# Headers.net
KiCad netlist of a schematic drawn in Altium Designer
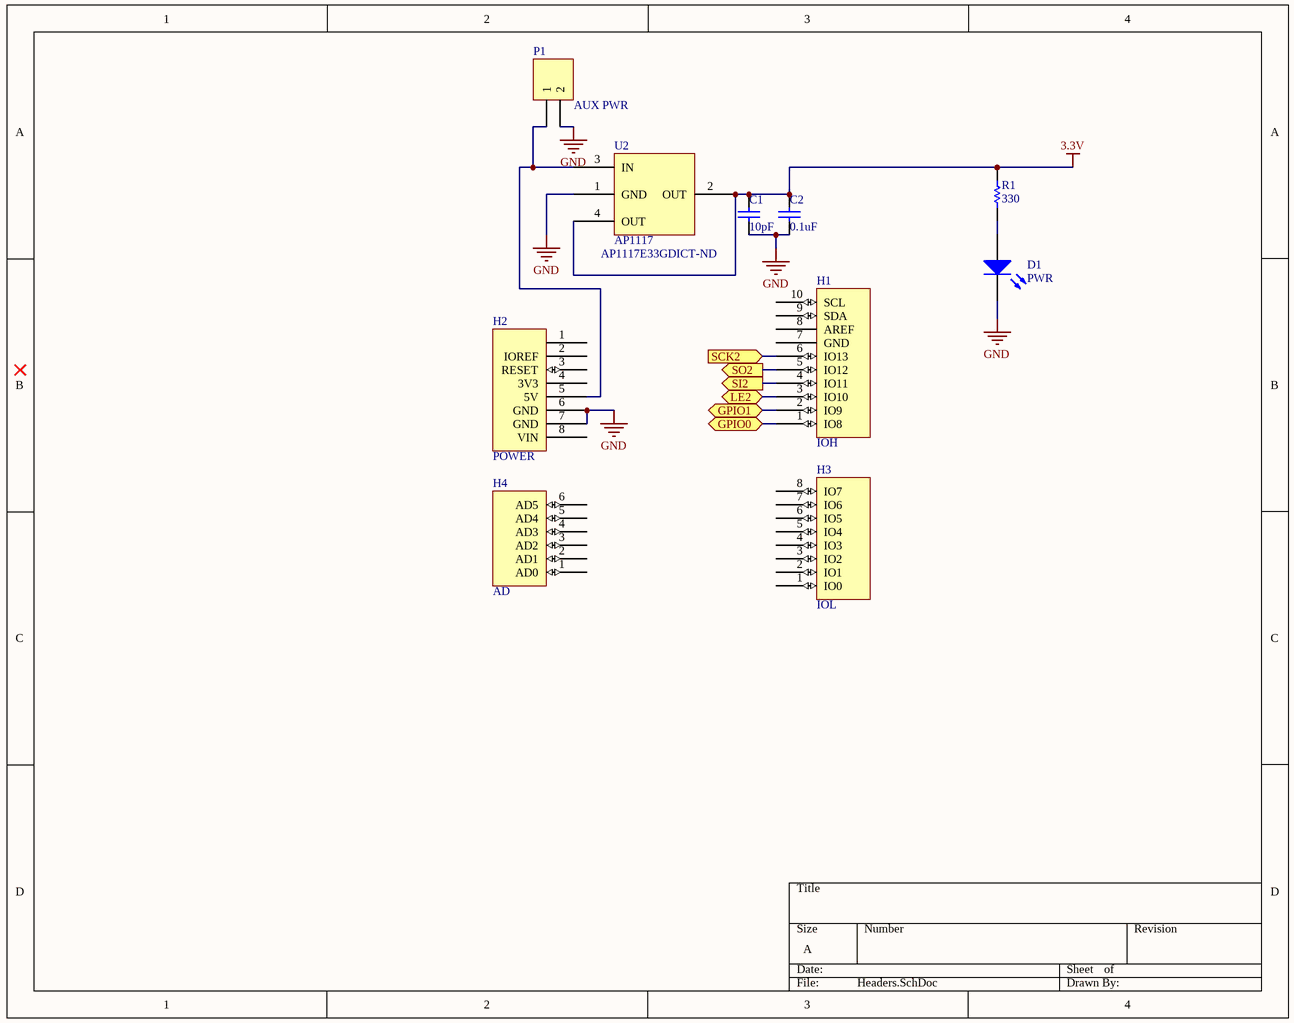
[diagram p0: Headers.SchDoc]

(export (version "E")
  (design (tool "Eeschema 10.0.6"))
  (components
    (comp (ref "C1")
      (value "10pF")
      (footprint "0402")
      (description "Capacitor (Semiconductor SIM Model)")
      (fields (field (name "Comment") "Cap Semi") (field (name "PUBLISHER") "Altium Limited"))
      (libsource (lib "Miscellaneous Devices") (part "Cap Semi"))
    )
    (comp (ref "C2")
      (value "0.1uF")
      (footprint "0402")
      (description "Capacitor (Semiconductor SIM Model)")
      (fields (field (name "Comment") "Cap Semi") (field (name "PUBLISHER") "Altium Limited"))
      (libsource (lib "Miscellaneous Devices") (part "Cap Semi"))
    )
    (comp (ref "D1")
      (value "PWR")
      (footprint "0603")
      (description "Typical RED, GREEN, YELLOW, AMBER GaAs LED")
      (fields (field (name "PUBLISHER") "Altium Limited"))
      (libsource (lib "Miscellaneous Devices") (part "LED2"))
    )
    (comp (ref "H1")
      (value "IOH")
      (footprint "Header:Header 10x1 8.5mm")
      (libsource (lib "Header") (part "IOH"))
    )
    (comp (ref "H2")
      (value "POWER")
      (footprint "Header:Header 8x1 8.5mm")
      (libsource (lib "Header") (part "POWER"))
    )
    (comp (ref "H3")
      (value "IOL")
      (footprint "Header:Header 8x1 8.5mm")
      (libsource (lib "Header") (part "IOL"))
    )
    (comp (ref "H4")
      (value "AD")
      (footprint "Header:Header 6x1 8.5mm")
      (libsource (lib "Header") (part "AD"))
    )
    (comp (ref "P1")
      (value "AUX PWR")
      (footprint "HDR1X2")
      (description "Header, 2-Pin")
      (fields (field (name "PUBLISHER") "Altium Limited"))
      (libsource (lib "Miscellaneous Connectors") (part "Header 2"))
    )
    (comp (ref "R1")
      (value "330")
      (footprint "0402")
      (description "Semiconductor Resistor")
      (fields (field (name "Comment") "Res Semi") (field (name "PUBLISHER") "Altium Limited"))
      (libsource (lib "Miscellaneous Devices") (part "Res Semi"))
    )
    (comp (ref "U2") (value "AP1117") (libsource (lib "shield_components") (part "AP1117")))
  )
  (nets
    (net (code "1") (name "/GPIO0") (class "Default")
      (node (ref "H1") (pin "1") (pinfunction "IO8_1") (pintype "bidirectional"))
    )
    (net (code "2") (name "/GPIO1") (class "Default")
      (node (ref "H1") (pin "2") (pinfunction "IO9_2") (pintype "bidirectional"))
    )
    (net (code "3") (name "/LE2") (class "Default")
      (node (ref "H1") (pin "3") (pinfunction "IO10_3") (pintype "bidirectional"))
    )
    (net (code "4") (name "/SCK2") (class "Default")
      (node (ref "H1") (pin "6") (pinfunction "IO13_6") (pintype "bidirectional"))
    )
    (net (code "5") (name "/SI2") (class "Default")
      (node (ref "H1") (pin "4") (pinfunction "IO11_4") (pintype "bidirectional"))
    )
    (net (code "6") (name "/SO2") (class "Default")
      (node (ref "H1") (pin "5") (pinfunction "IO12_5") (pintype "bidirectional"))
    )
    (net (code "7") (name "3.3V") (class "Default")
      (node (ref "C1") (pin "1") (pinfunction "1_1") (pintype "passive"))
      (node (ref "C2") (pin "1") (pinfunction "1_1") (pintype "passive"))
      (node (ref "R1") (pin "2") (pinfunction "2_2") (pintype "passive"))
      (node (ref "U2") (pin "2") (pinfunction "OUT_2") (pintype "passive"))
      (node (ref "U2") (pin "4") (pinfunction "OUT_4") (pintype "passive"))
    )
    (net (code "8") (name "GND") (class "Default")
      (node (ref "C1") (pin "2") (pinfunction "2_2") (pintype "passive"))
      (node (ref "C2") (pin "2") (pinfunction "2_2") (pintype "passive"))
      (node (ref "D1") (pin "2") (pinfunction "K_2") (pintype "passive"))
      (node (ref "H2") (pin "6") (pinfunction "GND_6") (pintype "power_in"))
      (node (ref "H2") (pin "7") (pinfunction "GND_7") (pintype "power_in"))
      (node (ref "P1") (pin "2") (pinfunction "2_2") (pintype "passive"))
      (node (ref "U2") (pin "1") (pinfunction "GND_1") (pintype "passive"))
    )
    (net (code "9") (name "Net-(D1-A)") (class "Default")
      (node (ref "D1") (pin "1") (pinfunction "A_1") (pintype "passive"))
      (node (ref "R1") (pin "1") (pinfunction "1_1") (pintype "passive"))
    )
    (net (code "10") (name "Net-(H2-5V)") (class "Default")
      (node (ref "H2") (pin "5") (pinfunction "5V_5") (pintype "power_in"))
      (node (ref "P1") (pin "1") (pinfunction "1_1") (pintype "passive"))
      (node (ref "U2") (pin "3") (pinfunction "IN_3") (pintype "passive"))
    )
    (net (code "11") (name "unconnected-(H1-AREF-Pad8)") (class "Default")
      (node (ref "H1") (pin "8") (pinfunction "AREF_8") (pintype "passive"))
    )
    (net (code "12") (name "unconnected-(H1-GND-Pad7)") (class "Default")
      (node (ref "H1") (pin "7") (pinfunction "GND_7") (pintype "power_in"))
    )
    (net (code "13") (name "unconnected-(H1-SCL-Pad10)") (class "Default")
      (node (ref "H1") (pin "10") (pinfunction "SCL_10") (pintype "bidirectional"))
    )
    (net (code "14") (name "unconnected-(H1-SDA-Pad9)") (class "Default")
      (node (ref "H1") (pin "9") (pinfunction "SDA_9") (pintype "bidirectional"))
    )
    (net (code "15") (name "unconnected-(H2-3V3-Pad4)") (class "Default")
      (node (ref "H2") (pin "4") (pinfunction "3V3_4") (pintype "power_in"))
    )
    (net (code "16") (name "unconnected-(H2-IOREF-Pad2)") (class "Default")
      (node (ref "H2") (pin "2") (pinfunction "IOREF_2") (pintype "power_in"))
    )
    (net (code "17") (name "unconnected-(H2-Pad1)") (class "Default")
      (node (ref "H2") (pin "1") (pintype "passive"))
    )
    (net (code "18") (name "unconnected-(H2-RESET-Pad3)") (class "Default")
      (node (ref "H2") (pin "3") (pinfunction "RESET_3") (pintype "bidirectional"))
    )
    (net (code "19") (name "unconnected-(H2-VIN-Pad8)") (class "Default")
      (node (ref "H2") (pin "8") (pinfunction "VIN_8") (pintype "power_in"))
    )
    (net (code "20") (name "unconnected-(H3-IO0-Pad1)") (class "Default")
      (node (ref "H3") (pin "1") (pinfunction "IO0_1") (pintype "bidirectional"))
    )
    (net (code "21") (name "unconnected-(H3-IO1-Pad2)") (class "Default")
      (node (ref "H3") (pin "2") (pinfunction "IO1_2") (pintype "bidirectional"))
    )
    (net (code "22") (name "unconnected-(H3-IO2-Pad3)") (class "Default")
      (node (ref "H3") (pin "3") (pinfunction "IO2_3") (pintype "bidirectional"))
    )
    (net (code "23") (name "unconnected-(H3-IO3-Pad4)") (class "Default")
      (node (ref "H3") (pin "4") (pinfunction "IO3_4") (pintype "bidirectional"))
    )
    (net (code "24") (name "unconnected-(H3-IO4-Pad5)") (class "Default")
      (node (ref "H3") (pin "5") (pinfunction "IO4_5") (pintype "bidirectional"))
    )
    (net (code "25") (name "unconnected-(H3-IO5-Pad6)") (class "Default")
      (node (ref "H3") (pin "6") (pinfunction "IO5_6") (pintype "bidirectional"))
    )
    (net (code "26") (name "unconnected-(H3-IO6-Pad7)") (class "Default")
      (node (ref "H3") (pin "7") (pinfunction "IO6_7") (pintype "bidirectional"))
    )
    (net (code "27") (name "unconnected-(H3-IO7-Pad8)") (class "Default")
      (node (ref "H3") (pin "8") (pinfunction "IO7_8") (pintype "bidirectional"))
    )
    (net (code "28") (name "unconnected-(H4-AD0-Pad1)") (class "Default")
      (node (ref "H4") (pin "1") (pinfunction "AD0_1") (pintype "bidirectional"))
    )
    (net (code "29") (name "unconnected-(H4-AD1-Pad2)") (class "Default")
      (node (ref "H4") (pin "2") (pinfunction "AD1_2") (pintype "bidirectional"))
    )
    (net (code "30") (name "unconnected-(H4-AD2-Pad3)") (class "Default")
      (node (ref "H4") (pin "3") (pinfunction "AD2_3") (pintype "bidirectional"))
    )
    (net (code "31") (name "unconnected-(H4-AD3-Pad4)") (class "Default")
      (node (ref "H4") (pin "4") (pinfunction "AD3_4") (pintype "bidirectional"))
    )
    (net (code "32") (name "unconnected-(H4-AD4-Pad5)") (class "Default")
      (node (ref "H4") (pin "5") (pinfunction "AD4_5") (pintype "bidirectional"))
    )
    (net (code "33") (name "unconnected-(H4-AD5-Pad6)") (class "Default")
      (node (ref "H4") (pin "6") (pinfunction "AD5_6") (pintype "bidirectional"))
    )
  )
)
